# pc_rpi_healthypi_v3.net
KiCad netlist of a schematic drawn in EAGLE
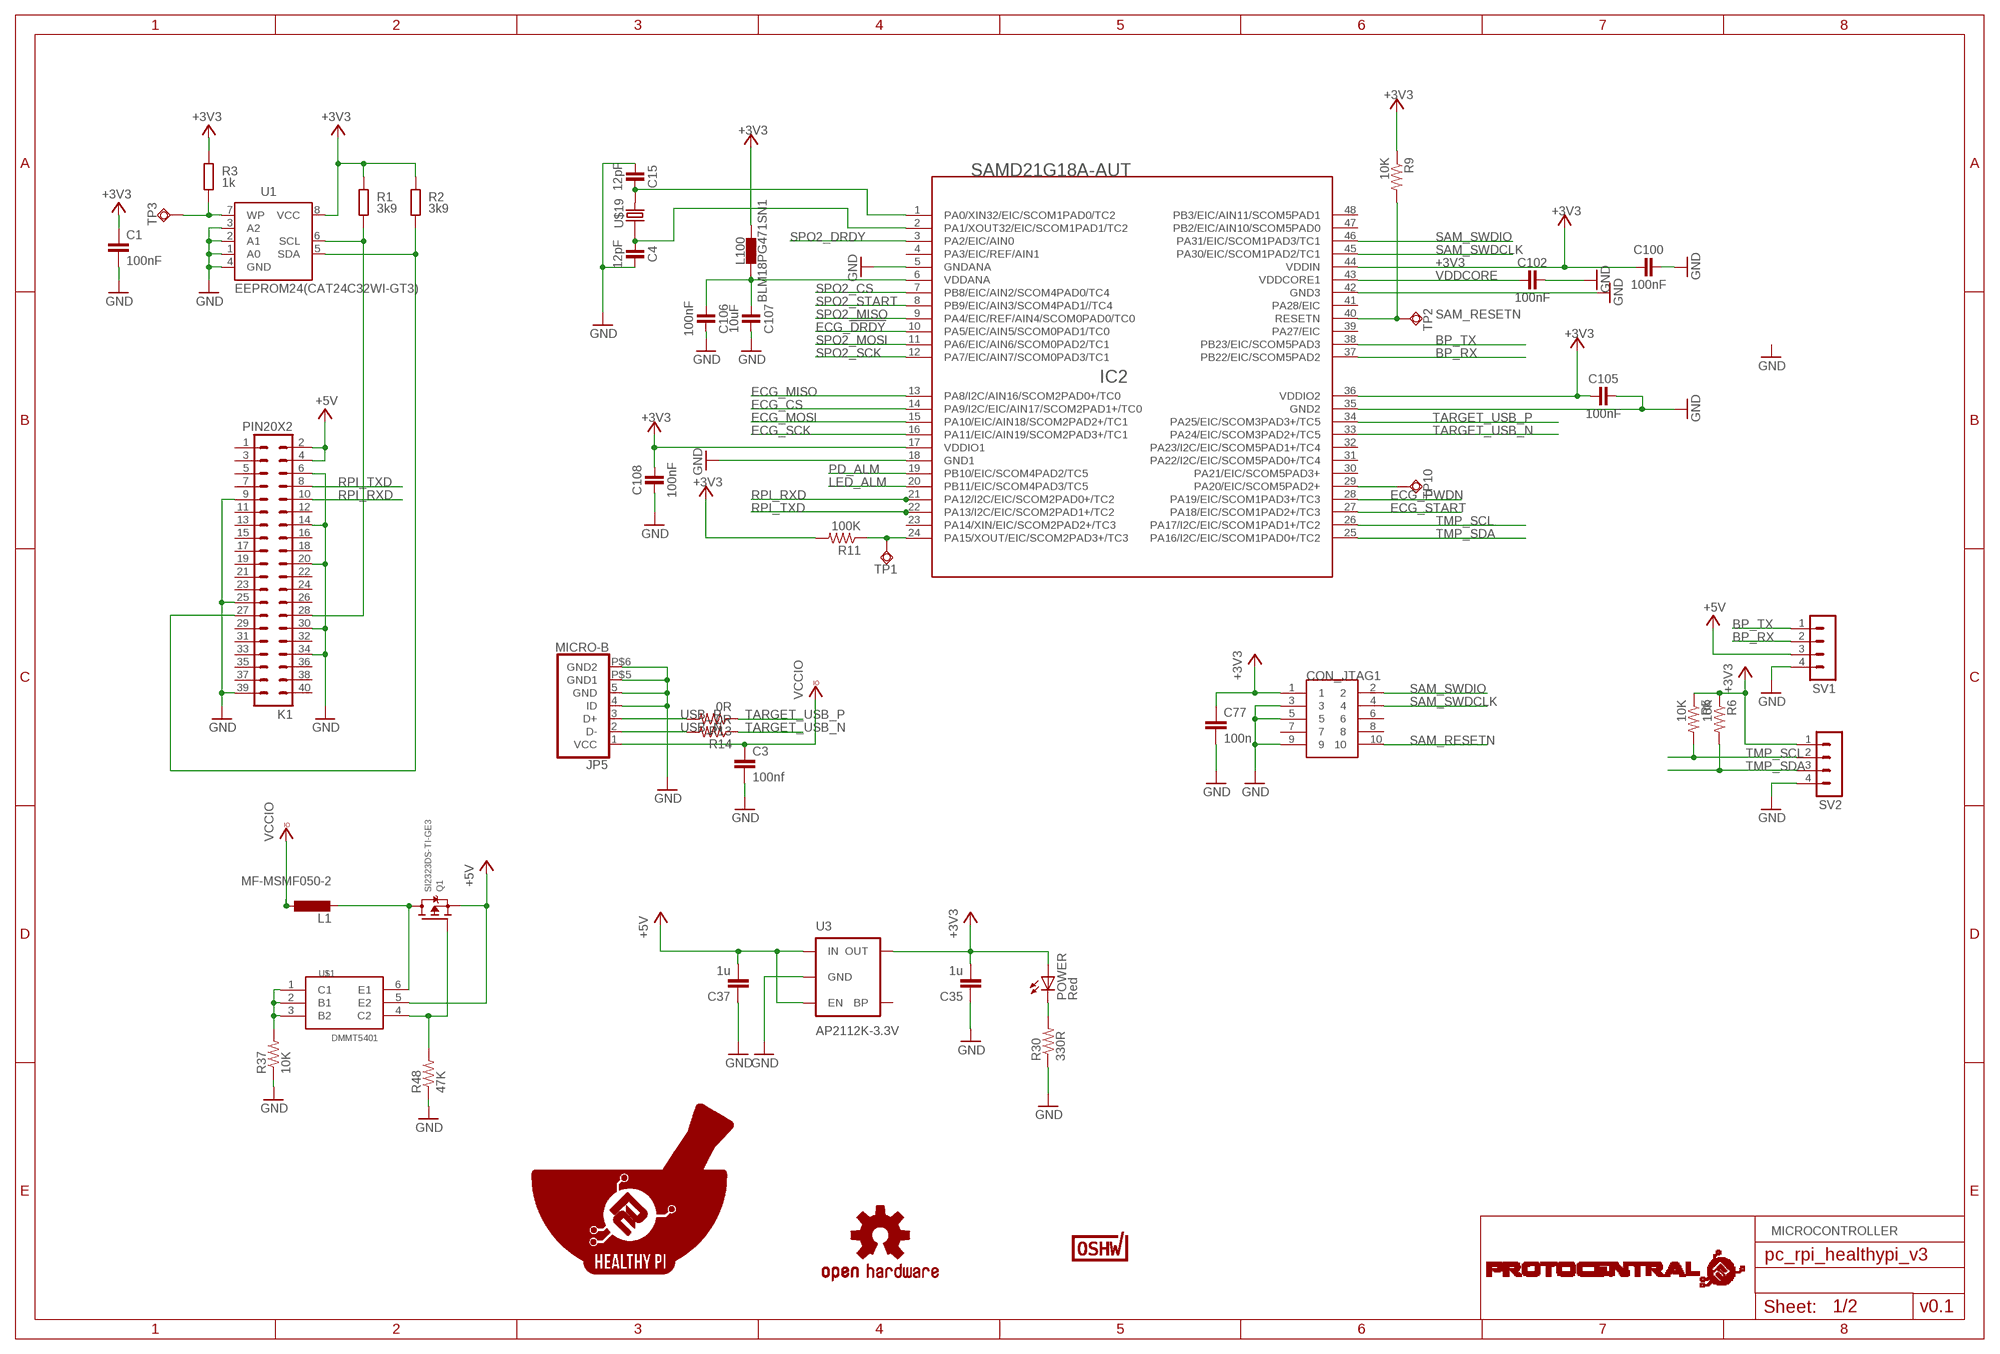
[diagram p0: schematic, sheet 1]
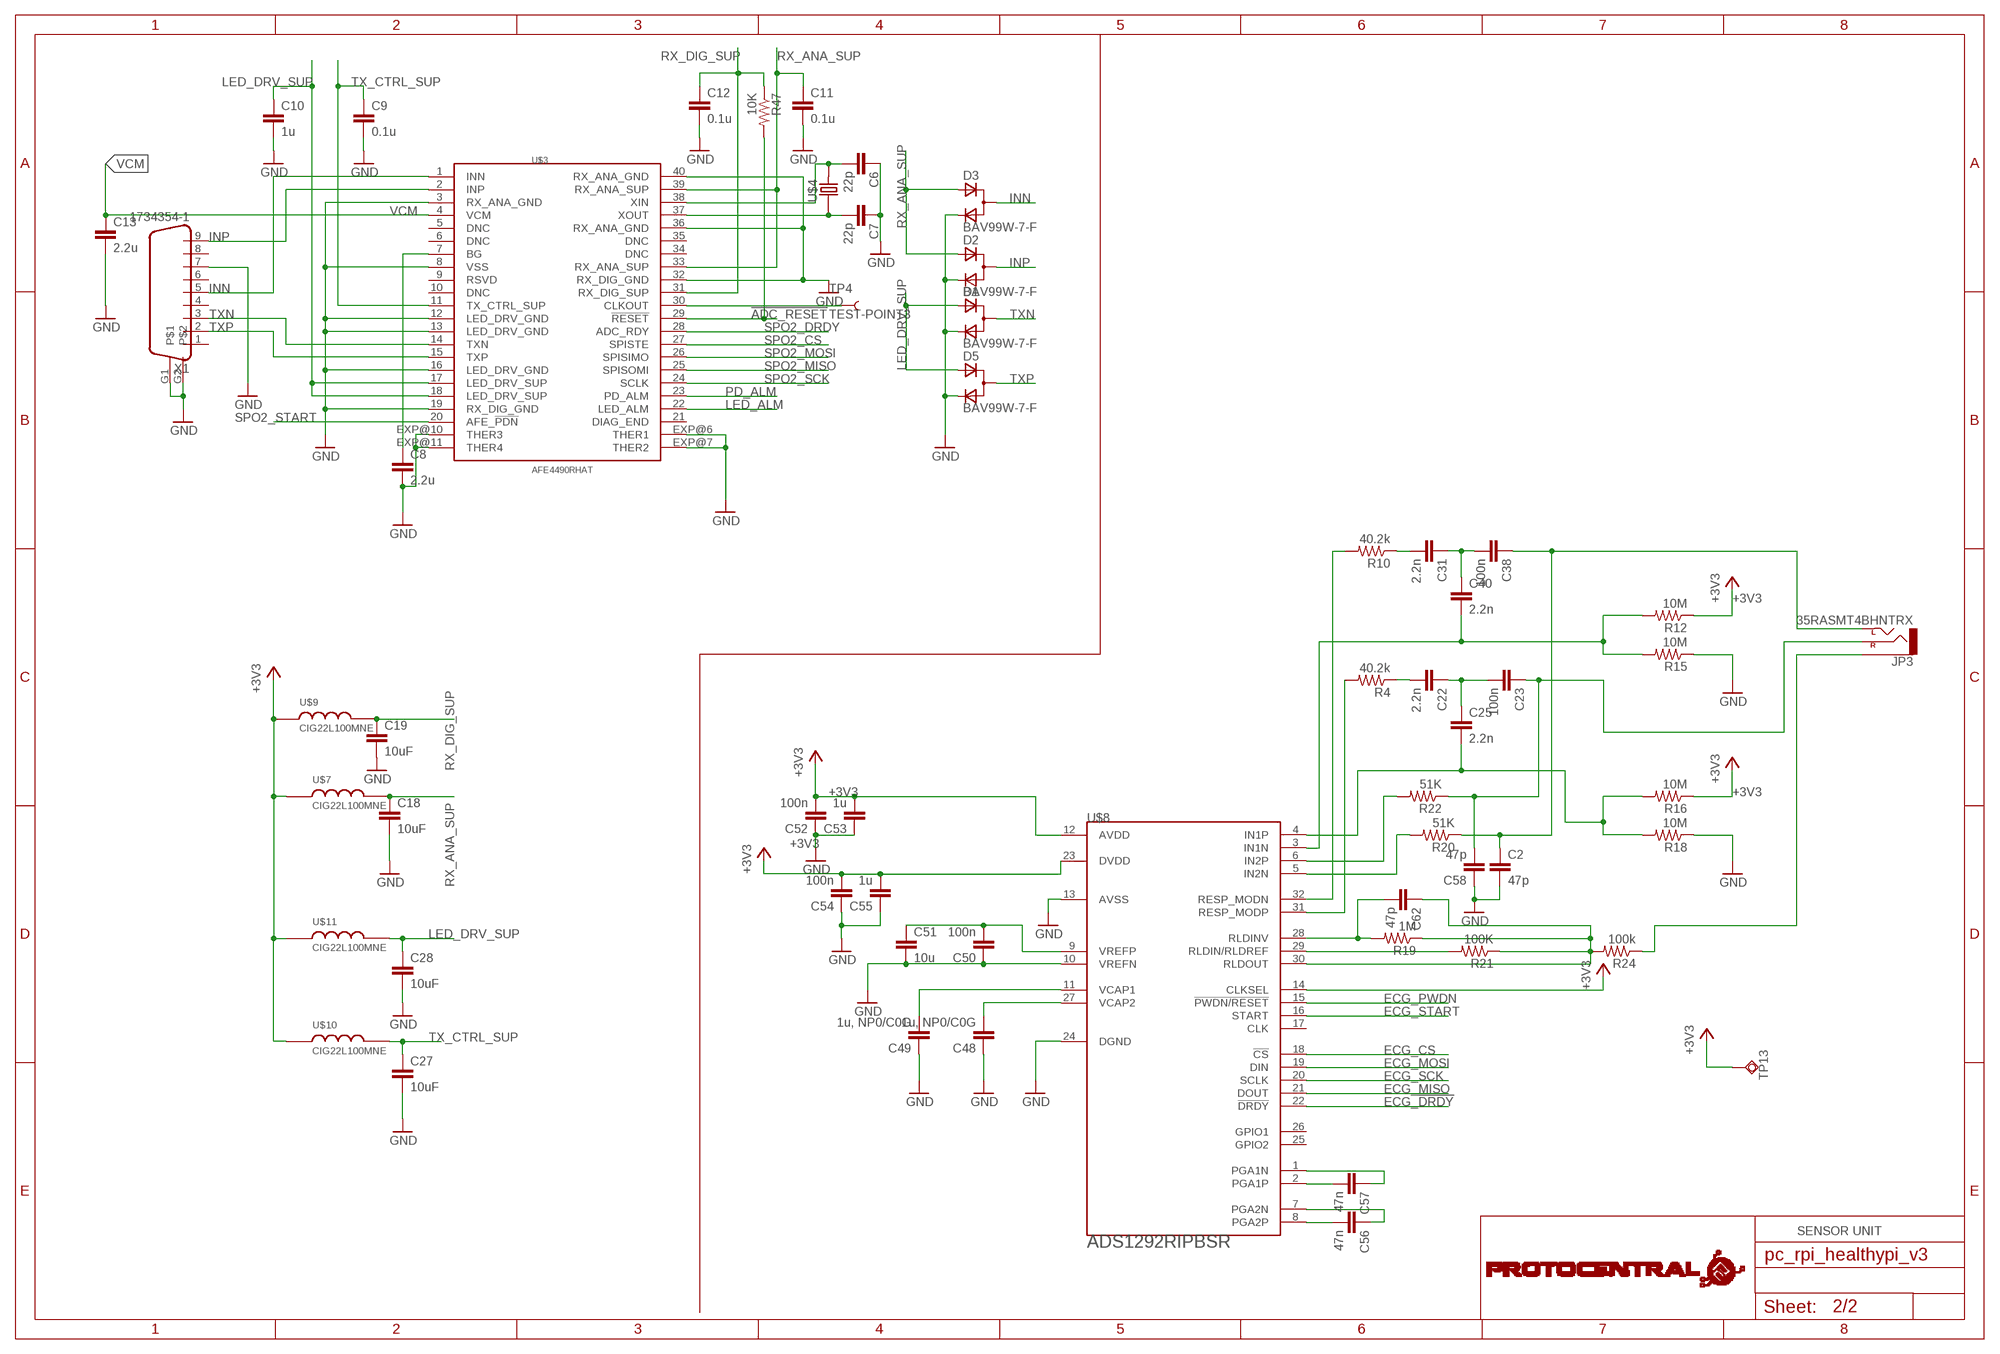
[diagram p1: schematic, sheet 2]

(export (version "E")
  (design (tool "Eeschema 10.0.6"))
  (components
    (comp (ref "C2")
      (value "47p")
      (footprint "eagle-import:C0402")
      (libsource (lib "eagle-import") (part "C-EUC0402"))
    )
    (comp (ref "C6")
      (value "22p")
      (footprint "eagle-import:C0402")
      (libsource (lib "eagle-import") (part "C-EUC0402"))
    )
    (comp (ref "C7")
      (value "22p")
      (footprint "eagle-import:C0402")
      (libsource (lib "eagle-import") (part "C-EUC0402"))
    )
    (comp (ref "C8")
      (value "2.2u")
      (footprint "eagle-import:C0402")
      (libsource (lib "eagle-import") (part "C-EUC0402"))
    )
    (comp (ref "C9")
      (value "0.1u")
      (footprint "eagle-import:C0402")
      (libsource (lib "eagle-import") (part "C-EUC0402"))
    )
    (comp (ref "C10")
      (value "1u")
      (footprint "eagle-import:C0805")
      (libsource (lib "eagle-import") (part "C-EUC0805"))
    )
    (comp (ref "C11")
      (value "0.1u")
      (footprint "eagle-import:C0402")
      (libsource (lib "eagle-import") (part "C-EUC0402"))
    )
    (comp (ref "C12")
      (value "0.1u")
      (footprint "eagle-import:C0402")
      (libsource (lib "eagle-import") (part "C-EUC0402"))
    )
    (comp (ref "C13")
      (value "2.2u")
      (footprint "eagle-import:C0402")
      (libsource (lib "eagle-import") (part "C-EUC0402"))
    )
    (comp (ref "C18")
      (value "10uF")
      (footprint "eagle-import:C0805")
      (libsource (lib "eagle-import") (part "C-EUC0805"))
    )
    (comp (ref "C19")
      (value "10uF")
      (footprint "eagle-import:C0805")
      (libsource (lib "eagle-import") (part "C-EUC0805"))
    )
    (comp (ref "C22")
      (value "2.2n")
      (footprint "eagle-import:C0402")
      (libsource (lib "eagle-import") (part "C-EUC0402"))
    )
    (comp (ref "C23")
      (value "100n")
      (footprint "eagle-import:C0402")
      (libsource (lib "eagle-import") (part "C-EUC0402"))
    )
    (comp (ref "C25")
      (value "2.2n")
      (footprint "eagle-import:C0402")
      (libsource (lib "eagle-import") (part "C-EUC0402"))
    )
    (comp (ref "C27")
      (value "10uF")
      (footprint "eagle-import:C0805")
      (libsource (lib "eagle-import") (part "C-EUC0805"))
    )
    (comp (ref "C28")
      (value "10uF")
      (footprint "eagle-import:C0805")
      (libsource (lib "eagle-import") (part "C-EUC0805"))
    )
    (comp (ref "C31")
      (value "2.2n")
      (footprint "eagle-import:C0402")
      (libsource (lib "eagle-import") (part "C-EUC0402"))
    )
    (comp (ref "C38")
      (value "100n")
      (footprint "eagle-import:C0402")
      (libsource (lib "eagle-import") (part "C-EUC0402"))
    )
    (comp (ref "C40")
      (value "2.2n")
      (footprint "eagle-import:C0402")
      (libsource (lib "eagle-import") (part "C-EUC0402"))
    )
    (comp (ref "C48")
      (value "1u, NP0/C0G")
      (footprint "eagle-import:C0402")
      (libsource (lib "eagle-import") (part "C-EUC0402"))
    )
    (comp (ref "C49")
      (value "1u, NP0/C0G")
      (footprint "eagle-import:C0402")
      (libsource (lib "eagle-import") (part "C-EUC0402"))
    )
    (comp (ref "C50")
      (value "100n")
      (footprint "eagle-import:C0402")
      (libsource (lib "eagle-import") (part "C-EUC0402"))
    )
    (comp (ref "C51")
      (value "10u")
      (footprint "eagle-import:C0603")
      (libsource (lib "eagle-import") (part "resistor_C-EUC0603"))
    )
    (comp (ref "C52")
      (value "100n")
      (footprint "eagle-import:C0402")
      (libsource (lib "eagle-import") (part "C-EUC0402"))
    )
    (comp (ref "C53")
      (value "1u")
      (footprint "eagle-import:C0402")
      (libsource (lib "eagle-import") (part "C-EUC0402"))
    )
    (comp (ref "C54")
      (value "100n")
      (footprint "eagle-import:C0402")
      (libsource (lib "eagle-import") (part "C-EUC0402"))
    )
    (comp (ref "C55")
      (value "1u")
      (footprint "eagle-import:C0402")
      (libsource (lib "eagle-import") (part "C-EUC0402"))
    )
    (comp (ref "C56")
      (value "47n")
      (footprint "eagle-import:C0402")
      (libsource (lib "eagle-import") (part "C-EUC0402"))
    )
    (comp (ref "C57")
      (value "47n")
      (footprint "eagle-import:C0402")
      (libsource (lib "eagle-import") (part "C-EUC0402"))
    )
    (comp (ref "C58")
      (value "47p")
      (footprint "eagle-import:C0402")
      (libsource (lib "eagle-import") (part "C-EUC0402"))
    )
    (comp (ref "C62")
      (value "47p")
      (footprint "eagle-import:C0402")
      (libsource (lib "eagle-import") (part "C-EUC0402"))
    )
    (comp (ref "D1")
      (value "BAV99W-7-F")
      (footprint "eagle-import:SOT323")
      (libsource (lib "eagle-import") (part "D_ACACSOT323"))
    )
    (comp (ref "D2")
      (value "BAV99W-7-F")
      (footprint "eagle-import:SOT323")
      (libsource (lib "eagle-import") (part "D_ACACSOT323"))
    )
    (comp (ref "D3")
      (value "BAV99W-7-F")
      (footprint "eagle-import:SOT323")
      (libsource (lib "eagle-import") (part "D_ACACSOT323"))
    )
    (comp (ref "D5")
      (value "BAV99W-7-F")
      (footprint "eagle-import:SOT323")
      (libsource (lib "eagle-import") (part "D_ACACSOT323"))
    )
    (comp (ref "JP3")
      (value "35RASMT4BHNTRX")
      (footprint "eagle-import:AUDIO-JACK-3.5MM-SMD")
      (libsource (lib "eagle-import") (part "AUDIO-JACKSMD2"))
    )
    (comp (ref "R4")
      (value "40.2k")
      (footprint "eagle-import:R0402")
      (libsource (lib "eagle-import") (part "R-US_R0402"))
    )
    (comp (ref "R10")
      (value "40.2k")
      (footprint "eagle-import:R0402")
      (libsource (lib "eagle-import") (part "R-US_R0402"))
    )
    (comp (ref "R12")
      (value "10M")
      (footprint "eagle-import:R0402")
      (libsource (lib "eagle-import") (part "R-US_R0402"))
    )
    (comp (ref "R15")
      (value "10M")
      (footprint "eagle-import:R0402")
      (libsource (lib "eagle-import") (part "R-US_R0402"))
    )
    (comp (ref "R16")
      (value "10M")
      (footprint "eagle-import:R0402")
      (libsource (lib "eagle-import") (part "R-US_R0402"))
    )
    (comp (ref "R18")
      (value "10M")
      (footprint "eagle-import:R0402")
      (libsource (lib "eagle-import") (part "R-US_R0402"))
    )
    (comp (ref "R19")
      (value "1M")
      (footprint "eagle-import:R0402")
      (libsource (lib "eagle-import") (part "R-US_R0402"))
    )
    (comp (ref "R20")
      (value "51K")
      (footprint "eagle-import:R0402")
      (libsource (lib "eagle-import") (part "R-US_R0402"))
    )
    (comp (ref "R21")
      (value "100K")
      (footprint "eagle-import:R0402")
      (libsource (lib "eagle-import") (part "R-US_R0402"))
    )
    (comp (ref "R22")
      (value "51K")
      (footprint "eagle-import:R0402")
      (libsource (lib "eagle-import") (part "R-US_R0402"))
    )
    (comp (ref "R24")
      (value "100k")
      (footprint "eagle-import:R0402")
      (libsource (lib "eagle-import") (part "R-US_R0402"))
    )
    (comp (ref "R47")
      (value "10K")
      (footprint "eagle-import:R0402")
      (libsource (lib "eagle-import") (part "R-US_R0402"))
    )
    (comp (ref "TP4")
      (value "TEST-POINT3")
      (footprint "eagle-import:PAD.03X.03")
      (libsource (lib "eagle-import") (part "TEST-POINT3"))
    )
    (comp (ref "TP13")
      (value "TPSQB1,27")
      (footprint "eagle-import:B1,27")
      (libsource (lib "eagle-import") (part "TPSQB1,27"))
    )
    (comp (ref "U$2")
      (value "PROTY_LOGO_WITH_TEXT")
      (footprint "eagle-import:PROTY_WITH_TEXT")
      (libsource (lib "eagle-import") (part "PROTY_LOGO_WITH_TEXT"))
    )
    (comp (ref "U$3")
      (value "AFE4490RHAT")
      (footprint "eagle-import:QFN-40")
      (libsource (lib "eagle-import") (part "AFE4400"))
    )
    (comp (ref "U$4")
      (value "ABM3")
      (footprint "eagle-import:ABM3")
      (libsource (lib "eagle-import") (part "ABM3"))
    )
    (comp (ref "U$7")
      (value "CIG22L100MNE")
      (footprint "eagle-import:LPS")
      (libsource (lib "eagle-import") (part "LPS"))
    )
    (comp (ref "U$8")
      (value "ADS1292RIPBSR")
      (footprint "eagle-import:SQFP-S-5X5-32")
      (libsource (lib "eagle-import") (part "ADS1292R-TQFP"))
    )
    (comp (ref "U$9")
      (value "CIG22L100MNE")
      (footprint "eagle-import:LPS")
      (libsource (lib "eagle-import") (part "LPS"))
    )
    (comp (ref "U$10")
      (value "CIG22L100MNE")
      (footprint "eagle-import:LPS")
      (libsource (lib "eagle-import") (part "LPS"))
    )
    (comp (ref "U$11")
      (value "CIG22L100MNE")
      (footprint "eagle-import:LPS")
      (libsource (lib "eagle-import") (part "LPS"))
    )
    (comp (ref "X1")
      (value "1734354-1")
      (footprint "eagle-import:DB9-STRIGHT")
      (libsource (lib "eagle-import") (part "DB9_STRIGHT"))
    )
    (comp (ref "C1")
      (value "100nF")
      (footprint "eagle-import:C0805K")
      (libsource (lib "eagle-import") (part "resistor_C-EUC0805K"))
    )
    (comp (ref "C3")
      (value "100nf")
      (footprint "eagle-import:C0402")
      (libsource (lib "eagle-import") (part "C-EUC0402"))
    )
    (comp (ref "C4")
      (value "12pF")
      (footprint "eagle-import:C0402")
      (libsource (lib "eagle-import") (part "CAPACITORS-0402"))
    )
    (comp (ref "C15")
      (value "12pF")
      (footprint "eagle-import:C0402")
      (libsource (lib "eagle-import") (part "CAPACITORS-0402"))
    )
    (comp (ref "C35")
      (value "1u")
      (footprint "eagle-import:C0402")
      (libsource (lib "eagle-import") (part "C-EUC0402"))
    )
    (comp (ref "C37")
      (value "1u")
      (footprint "eagle-import:C0402")
      (libsource (lib "eagle-import") (part "C-EUC0402"))
    )
    (comp (ref "C77")
      (value "100n")
      (footprint "eagle-import:C0805")
      (libsource (lib "eagle-import") (part "C-EUC0805"))
    )
    (comp (ref "C100")
      (value "100nF")
      (footprint "eagle-import:C0805")
      (libsource (lib "eagle-import") (part "CAPACITORS-0805"))
    )
    (comp (ref "C102")
      (value "100nF")
      (footprint "eagle-import:C0805")
      (libsource (lib "eagle-import") (part "CAPACITORS-0805"))
    )
    (comp (ref "C105")
      (value "100nF")
      (footprint "eagle-import:C0805")
      (libsource (lib "eagle-import") (part "CAPACITORS-0805"))
    )
    (comp (ref "C106")
      (value "100nF")
      (footprint "eagle-import:C0805")
      (libsource (lib "eagle-import") (part "CAPACITORS-0805"))
    )
    (comp (ref "C107")
      (value "10uF")
      (footprint "eagle-import:C0805")
      (libsource (lib "eagle-import") (part "CAPACITORS-0805"))
    )
    (comp (ref "C108")
      (value "100nF")
      (footprint "eagle-import:C0805")
      (libsource (lib "eagle-import") (part "CAPACITORS-0805"))
    )
    (comp (ref "CON_JTAG1")
      (value "HDR-SMT-50MIL/5X2(20021121-00010C4LF)")
      (footprint "eagle-import:HDR-SMT-50MIL_5X2")
      (libsource (lib "eagle-import") (part "HDR-SMT-50MIL/5X2"))
    )
    (comp (ref "IC2")
      (value "SAMD21G18A-AUT")
      (footprint "eagle-import:TQFP48")
      (libsource (lib "eagle-import") (part "SAMD21G18A"))
    )
    (comp (ref "JP5")
      (value "MICRO-B")
      (footprint "eagle-import:MICRO-B")
      (libsource (lib "eagle-import") (part "MICRO-B"))
    )
    (comp (ref "K1")
      (value "PIN20X2")
      (footprint "eagle-import:PIN_20X2")
      (libsource (lib "eagle-import") (part "PIN20X2"))
    )
    (comp (ref "L1")
      (value "MF-MSMF050-2")
      (footprint "eagle-import:L1812")
      (libsource (lib "eagle-import") (part "L-EUL1812"))
    )
    (comp (ref "L100")
      (value "BLM18PG471SN1")
      (footprint "eagle-import:C0603")
      (libsource (lib "eagle-import") (part "INDUCTOR-0603"))
    )
    (comp (ref "POWER")
      (value "Red")
      (footprint "eagle-import:CHIPLED_0603")
      (libsource (lib "eagle-import") (part "LEDCHIPLED_0603"))
    )
    (comp (ref "Q1")
      (value "SI2323DS-TI-GE3")
      (footprint "eagle-import:SOT23-R")
      (libsource (lib "eagle-import") (part "MOSFET-P"))
    )
    (comp (ref "R1")
      (value "3k9")
      (footprint "eagle-import:M0805")
      (fields (field (name "TOLERANCE") "5%"))
      (libsource (lib "eagle-import") (part "R-EU_M0805"))
    )
    (comp (ref "R2")
      (value "3k9")
      (footprint "eagle-import:M0805")
      (fields (field (name "TOLERANCE") "5%"))
      (libsource (lib "eagle-import") (part "R-EU_M0805"))
    )
    (comp (ref "R3")
      (value "1k")
      (footprint "eagle-import:M0805")
      (fields (field (name "TOLERANCE") "5%"))
      (libsource (lib "eagle-import") (part "R-EU_M0805"))
    )
    (comp (ref "R5")
      (value "10K")
      (footprint "eagle-import:R0402")
      (libsource (lib "eagle-import") (part "R-US_R0402"))
    )
    (comp (ref "R6")
      (value "10K")
      (footprint "eagle-import:R0402")
      (libsource (lib "eagle-import") (part "R-US_R0402"))
    )
    (comp (ref "R9")
      (value "10K")
      (footprint "eagle-import:R0805")
      (libsource (lib "eagle-import") (part "R-US_R0805"))
    )
    (comp (ref "R11")
      (value "100K")
      (footprint "eagle-import:R0805")
      (libsource (lib "eagle-import") (part "R-US_R0805"))
    )
    (comp (ref "R13")
      (value "0R")
      (footprint "eagle-import:R0402")
      (libsource (lib "eagle-import") (part "R-US_R0402"))
    )
    (comp (ref "R14")
      (value "0R")
      (footprint "eagle-import:R0402")
      (libsource (lib "eagle-import") (part "R-US_R0402"))
    )
    (comp (ref "R30")
      (value "330R")
      (footprint "eagle-import:R0402")
      (libsource (lib "eagle-import") (part "R-US_R0402"))
    )
    (comp (ref "R37")
      (value "10K")
      (footprint "eagle-import:R0805")
      (libsource (lib "eagle-import") (part "R-US_R0805"))
    )
    (comp (ref "R48")
      (value "47K")
      (footprint "eagle-import:R0805")
      (libsource (lib "eagle-import") (part "R-US_R0805"))
    )
    (comp (ref "SV1")
      (value "MA04-1")
      (footprint "eagle-import:MA04-1")
      (libsource (lib "eagle-import") (part "MA04-1"))
    )
    (comp (ref "SV2")
      (value "MA04-1")
      (footprint "eagle-import:MA04-1")
      (libsource (lib "eagle-import") (part "MA04-1"))
    )
    (comp (ref "TP1")
      (value "TPSQB1,27")
      (footprint "eagle-import:B1,27")
      (libsource (lib "eagle-import") (part "TPSQB1,27"))
    )
    (comp (ref "TP2")
      (value "TPSQB1,27")
      (footprint "eagle-import:B1,27")
      (libsource (lib "eagle-import") (part "TPSQB1,27"))
    )
    (comp (ref "TP3")
      (value "TPSQB1,27")
      (footprint "eagle-import:B1,27")
      (libsource (lib "eagle-import") (part "TPSQB1,27"))
    )
    (comp (ref "TP10")
      (value "TPSQB1,27")
      (footprint "eagle-import:B1,27")
      (libsource (lib "eagle-import") (part "TPSQB1,27"))
    )
    (comp (ref "U$1")
      (value "DMMT5401")
      (footprint "eagle-import:SOT26")
      (libsource (lib "eagle-import") (part "DMMT5401"))
    )
    (comp (ref "U$5")
      (value "OSHW-LOGOM")
      (footprint "eagle-import:OSHW-LOGO-M")
      (libsource (lib "eagle-import") (part "OSHW-LOGOM"))
    )
    (comp (ref "U$6")
      (value "PROTY_LOGO_WITH_TEXT")
      (footprint "eagle-import:PROTY_WITH_TEXT")
      (libsource (lib "eagle-import") (part "PROTY_LOGO_WITH_TEXT"))
    )
    (comp (ref "U$13")
      (value "CERT-SMALL")
      (footprint "eagle-import:CERT-SMALL-SILK")
      (libsource (lib "eagle-import") (part "CERT-SMALL"))
    )
    (comp (ref "U$15")
      (value "HEALTHYPI")
      (footprint "eagle-import:HEALTHYPI")
      (libsource (lib "eagle-import") (part "HEALTHYPI"))
    )
    (comp (ref "U$19")
      (value "520-327-12.5-34B(32.768KHZ)")
      (footprint "eagle-import:ECX-31B")
      (libsource (lib "eagle-import") (part "ECS-X-34B"))
    )
    (comp (ref "U1")
      (value "EEPROM24(CAT24C32WI-GT3)")
      (footprint "eagle-import:SOIC8")
      (libsource (lib "eagle-import") (part "EEPROM24"))
    )
    (comp (ref "U3")
      (value "AP2112K-3.3V")
      (footprint "eagle-import:SOT23-5")
      (libsource (lib "eagle-import") (part "V_REG_LDOSMD"))
    )
  )
  (nets
    (net (code "1") (name "+3V3") (class "Default")
      (node (ref "C1") (pin "1") (pinfunction "1_1") (pintype "passive"))
      (node (ref "C100") (pin "1") (pinfunction "1_1") (pintype "passive"))
      (node (ref "C105") (pin "1") (pinfunction "1_1") (pintype "passive"))
      (node (ref "C108") (pin "2") (pinfunction "2_2") (pintype "passive"))
      (node (ref "C35") (pin "2") (pinfunction "2_2") (pintype "passive"))
      (node (ref "C52") (pin "2") (pinfunction "2_2") (pintype "passive"))
      (node (ref "C53") (pin "2") (pinfunction "2_2") (pintype "passive"))
      (node (ref "C54") (pin "2") (pinfunction "2_2") (pintype "passive"))
      (node (ref "C55") (pin "2") (pinfunction "2_2") (pintype "passive"))
      (node (ref "C77") (pin "1") (pinfunction "1_1") (pintype "passive"))
      (node (ref "CON_JTAG1") (pin "1") (pinfunction "1_1") (pintype "bidirectional"))
      (node (ref "IC2") (pin "17") (pinfunction "VDDIO1_17") (pintype "power_in"))
      (node (ref "IC2") (pin "36") (pinfunction "VDDIO2_36") (pintype "power_in"))
      (node (ref "IC2") (pin "44") (pinfunction "VDDIN_44") (pintype "power_in"))
      (node (ref "L100") (pin "2") (pinfunction "2_2") (pintype "passive"))
      (node (ref "POWER") (pin "A") (pinfunction "A_A") (pintype "passive"))
      (node (ref "R1") (pin "2") (pinfunction "2_2") (pintype "passive"))
      (node (ref "R11") (pin "2") (pinfunction "2_2") (pintype "passive"))
      (node (ref "R12") (pin "1") (pinfunction "1_1") (pintype "passive"))
      (node (ref "R16") (pin "1") (pinfunction "1_1") (pintype "passive"))
      (node (ref "R2") (pin "2") (pinfunction "2_2") (pintype "passive"))
      (node (ref "R3") (pin "2") (pinfunction "2_2") (pintype "passive"))
      (node (ref "R5") (pin "1") (pinfunction "1_1") (pintype "passive"))
      (node (ref "R6") (pin "1") (pinfunction "1_1") (pintype "passive"))
      (node (ref "R9") (pin "1") (pinfunction "1_1") (pintype "passive"))
      (node (ref "SV2") (pin "1") (pinfunction "1_1") (pintype "passive"))
      (node (ref "TP13") (pin "TP") (pinfunction "TP_TP") (pintype "input"))
      (node (ref "U$10") (pin "1") (pinfunction "P$1_1") (pintype "bidirectional"))
      (node (ref "U$11") (pin "1") (pinfunction "P$1_1") (pintype "bidirectional"))
      (node (ref "U$7") (pin "1") (pinfunction "P$1_1") (pintype "bidirectional"))
      (node (ref "U$8") (pin "12") (pinfunction "AVDD_12") (pintype "power_in"))
      (node (ref "U$8") (pin "14") (pinfunction "CLKSEL_14") (pintype "bidirectional"))
      (node (ref "U$8") (pin "23") (pinfunction "DVDD_23") (pintype "power_in"))
      (node (ref "U$9") (pin "1") (pinfunction "P$1_1") (pintype "bidirectional"))
      (node (ref "U1") (pin "8") (pinfunction "VCC_8") (pintype "power_in"))
      (node (ref "U3") (pin "5") (pinfunction "OUT_5") (pintype "passive"))
    )
    (net (code "2") (name "+5V") (class "Default")
      (node (ref "C37") (pin "2") (pinfunction "2_2") (pintype "passive"))
      (node (ref "K1") (pin "2") (pinfunction "2_2") (pintype "passive"))
      (node (ref "K1") (pin "4") (pinfunction "4_4") (pintype "passive"))
      (node (ref "Q1") (pin "2") (pinfunction "S_2") (pintype "passive"))
      (node (ref "SV1") (pin "3") (pinfunction "3_3") (pintype "passive"))
      (node (ref "U$1") (pin "5") (pinfunction "E2_5") (pintype "bidirectional"))
      (node (ref "U3") (pin "1") (pinfunction "IN_1") (pintype "input"))
      (node (ref "U3") (pin "3") (pinfunction "EN_3") (pintype "input"))
    )
    (net (code "3") (name "BP_RX") (class "Default")
      (node (ref "IC2") (pin "37") (pinfunction "PB22/EIC/SCOM5PAD2_37") (pintype "bidirectional"))
      (node (ref "SV1") (pin "2") (pinfunction "2_2") (pintype "passive"))
    )
    (net (code "4") (name "BP_TX") (class "Default")
      (node (ref "IC2") (pin "38") (pinfunction "PB23/EIC/SCOM5PAD3_38") (pintype "bidirectional"))
      (node (ref "SV1") (pin "1") (pinfunction "1_1") (pintype "passive"))
    )
    (net (code "5") (name "ECG_CS") (class "Default")
      (node (ref "IC2") (pin "14") (pinfunction "PA9/I2C/EIC/AIN17/SCOM2PAD1+/TC0_14") (pintype "bidirectional"))
      (node (ref "U$8") (pin "18") (pinfunction "~{CS}_18") (pintype "bidirectional"))
    )
    (net (code "6") (name "ECG_MISO") (class "Default")
      (node (ref "IC2") (pin "13") (pinfunction "PA8/I2C/AIN16/SCOM2PAD0+/TC0_13") (pintype "bidirectional"))
      (node (ref "U$8") (pin "21") (pinfunction "DOUT_21") (pintype "bidirectional"))
    )
    (net (code "7") (name "ECG_MOSI") (class "Default")
      (node (ref "IC2") (pin "15") (pinfunction "PA10/EIC/AIN18/SCOM2PAD2+/TC1_15") (pintype "bidirectional"))
      (node (ref "U$8") (pin "19") (pinfunction "DIN_19") (pintype "bidirectional"))
    )
    (net (code "8") (name "ECG_PWDN") (class "Default")
      (node (ref "IC2") (pin "28") (pinfunction "PA19/EIC/SCOM1PAD3+/TC3_28") (pintype "bidirectional"))
      (node (ref "U$8") (pin "15") (pinfunction "~{PWDN/RESET}_15") (pintype "bidirectional"))
    )
    (net (code "9") (name "ECG_SCK") (class "Default")
      (node (ref "IC2") (pin "16") (pinfunction "PA11/EIC/AIN19/SCOM2PAD3+/TC1_16") (pintype "bidirectional"))
      (node (ref "U$8") (pin "20") (pinfunction "SCLK_20") (pintype "bidirectional"))
    )
    (net (code "10") (name "ECG_START") (class "Default")
      (node (ref "IC2") (pin "27") (pinfunction "PA18/EIC/SCOM1PAD2+/TC3_27") (pintype "bidirectional"))
      (node (ref "U$8") (pin "16") (pinfunction "START_16") (pintype "bidirectional"))
    )
    (net (code "11") (name "ECG_~{DRDY}") (class "Default")
      (node (ref "IC2") (pin "10") (pinfunction "PA5/EIC/AIN5/SCOM0PAD1/TC0_10") (pintype "bidirectional"))
      (node (ref "U$8") (pin "22") (pinfunction "~{DRDY}_22") (pintype "bidirectional"))
    )
    (net (code "12") (name "GND") (class "Default")
      (node (ref "C1") (pin "2") (pinfunction "2_2") (pintype "passive"))
      (node (ref "C10") (pin "2") (pinfunction "2_2") (pintype "passive"))
      (node (ref "C100") (pin "2") (pinfunction "2_2") (pintype "passive"))
      (node (ref "C102") (pin "2") (pinfunction "2_2") (pintype "passive"))
      (node (ref "C105") (pin "2") (pinfunction "2_2") (pintype "passive"))
      (node (ref "C106") (pin "2") (pinfunction "2_2") (pintype "passive"))
      (node (ref "C107") (pin "2") (pinfunction "2_2") (pintype "passive"))
      (node (ref "C108") (pin "1") (pinfunction "1_1") (pintype "passive"))
      (node (ref "C11") (pin "2") (pinfunction "2_2") (pintype "passive"))
      (node (ref "C12") (pin "2") (pinfunction "2_2") (pintype "passive"))
      (node (ref "C13") (pin "2") (pinfunction "2_2") (pintype "passive"))
      (node (ref "C15") (pin "1") (pinfunction "1_1") (pintype "passive"))
      (node (ref "C18") (pin "2") (pinfunction "2_2") (pintype "passive"))
      (node (ref "C19") (pin "2") (pinfunction "2_2") (pintype "passive"))
      (node (ref "C2") (pin "2") (pinfunction "2_2") (pintype "passive"))
      (node (ref "C27") (pin "2") (pinfunction "2_2") (pintype "passive"))
      (node (ref "C28") (pin "2") (pinfunction "2_2") (pintype "passive"))
      (node (ref "C3") (pin "2") (pinfunction "2_2") (pintype "passive"))
      (node (ref "C35") (pin "1") (pinfunction "1_1") (pintype "passive"))
      (node (ref "C37") (pin "1") (pinfunction "1_1") (pintype "passive"))
      (node (ref "C4") (pin "2") (pinfunction "2_2") (pintype "passive"))
      (node (ref "C48") (pin "1") (pinfunction "1_1") (pintype "passive"))
      (node (ref "C49") (pin "1") (pinfunction "1_1") (pintype "passive"))
      (node (ref "C50") (pin "1") (pinfunction "1_1") (pintype "passive"))
      (node (ref "C51") (pin "2") (pinfunction "2_2") (pintype "passive"))
      (node (ref "C52") (pin "1") (pinfunction "1_1") (pintype "passive"))
      (node (ref "C53") (pin "1") (pinfunction "1_1") (pintype "passive"))
      (node (ref "C54") (pin "1") (pinfunction "1_1") (pintype "passive"))
      (node (ref "C55") (pin "1") (pinfunction "1_1") (pintype "passive"))
      (node (ref "C58") (pin "1") (pinfunction "1_1") (pintype "passive"))
      (node (ref "C6") (pin "1") (pinfunction "1_1") (pintype "passive"))
      (node (ref "C7") (pin "1") (pinfunction "1_1") (pintype "passive"))
      (node (ref "C77") (pin "2") (pinfunction "2_2") (pintype "passive"))
      (node (ref "C8") (pin "2") (pinfunction "2_2") (pintype "passive"))
      (node (ref "C9") (pin "2") (pinfunction "2_2") (pintype "passive"))
      (node (ref "CON_JTAG1") (pin "3") (pinfunction "3_3") (pintype "bidirectional"))
      (node (ref "CON_JTAG1") (pin "5") (pinfunction "5_5") (pintype "bidirectional"))
      (node (ref "CON_JTAG1") (pin "9") (pinfunction "9_9") (pintype "bidirectional"))
      (node (ref "D1") (pin "2") (pinfunction "C_2") (pintype "passive"))
      (node (ref "D2") (pin "2") (pinfunction "C_2") (pintype "passive"))
      (node (ref "D3") (pin "2") (pinfunction "C_2") (pintype "passive"))
      (node (ref "D5") (pin "2") (pinfunction "C_2") (pintype "passive"))
      (node (ref "IC2") (pin "18") (pinfunction "GND1_18") (pintype "power_in"))
      (node (ref "IC2") (pin "35") (pinfunction "GND2_35") (pintype "power_in"))
      (node (ref "IC2") (pin "42") (pinfunction "GND3_42") (pintype "power_in"))
      (node (ref "IC2") (pin "5") (pinfunction "GNDANA_5") (pintype "power_in"))
      (node (ref "JP5") (pin "4") (pinfunction "ID_4") (pintype "bidirectional"))
      (node (ref "JP5") (pin "5") (pinfunction "GND_5") (pintype "bidirectional"))
      (node (ref "JP5") (pin "P$5") (pinfunction "GND1_P$5") (pintype "bidirectional"))
      (node (ref "JP5") (pin "P$6") (pinfunction "GND2_P$6") (pintype "bidirectional"))
      (node (ref "K1") (pin "14") (pinfunction "14_14") (pintype "passive"))
      (node (ref "K1") (pin "20") (pinfunction "20_20") (pintype "passive"))
      (node (ref "K1") (pin "25") (pinfunction "25_25") (pintype "passive"))
      (node (ref "K1") (pin "30") (pinfunction "30_30") (pintype "passive"))
      (node (ref "K1") (pin "34") (pinfunction "34_34") (pintype "passive"))
      (node (ref "K1") (pin "39") (pinfunction "39_39") (pintype "passive"))
      (node (ref "K1") (pin "6") (pinfunction "6_6") (pintype "passive"))
      (node (ref "K1") (pin "9") (pinfunction "9_9") (pintype "passive"))
      (node (ref "R15") (pin "1") (pinfunction "1_1") (pintype "passive"))
      (node (ref "R18") (pin "1") (pinfunction "1_1") (pintype "passive"))
      (node (ref "R30") (pin "1") (pinfunction "1_1") (pintype "passive"))
      (node (ref "R37") (pin "1") (pinfunction "1_1") (pintype "passive"))
      (node (ref "R48") (pin "1") (pinfunction "1_1") (pintype "passive"))
      (node (ref "SV1") (pin "4") (pinfunction "4_4") (pintype "passive"))
      (node (ref "SV2") (pin "4") (pinfunction "4_4") (pintype "passive"))
      (node (ref "U$3") (pin "12") (pinfunction "LED_DRV_GND_12") (pintype "bidirectional"))
      (node (ref "U$3") (pin "13") (pinfunction "LED_DRV_GND_13") (pintype "bidirectional"))
      (node (ref "U$3") (pin "16") (pinfunction "LED_DRV_GND_16") (pintype "bidirectional"))
      (node (ref "U$3") (pin "19") (pinfunction "RX_DIG_GND_19") (pintype "bidirectional"))
      (node (ref "U$3") (pin "3") (pinfunction "RX_ANA_GND_3") (pintype "bidirectional"))
      (node (ref "U$3") (pin "32") (pinfunction "RX_DIG_GND_32") (pintype "bidirectional"))
      (node (ref "U$3") (pin "36") (pinfunction "RX_ANA_GND_36") (pintype "bidirectional"))
      (node (ref "U$3") (pin "40") (pinfunction "RX_ANA_GND_40") (pintype "bidirectional"))
      (node (ref "U$3") (pin "8") (pinfunction "VSS_8") (pintype "bidirectional"))
      (node (ref "U$3") (pin "EXP@10") (pinfunction "THER3_EXP@10") (pintype "bidirectional"))
      (node (ref "U$3") (pin "EXP@11") (pinfunction "THER4_EXP@11") (pintype "bidirectional"))
      (node (ref "U$3") (pin "EXP@6") (pinfunction "THER1_EXP@6") (pintype "bidirectional"))
      (node (ref "U$3") (pin "EXP@7") (pinfunction "THER2_EXP@7") (pintype "bidirectional"))
      (node (ref "U$8") (pin "10") (pinfunction "VREFN_10") (pintype "bidirectional"))
      (node (ref "U$8") (pin "13") (pinfunction "AVSS_13") (pintype "bidirectional"))
      (node (ref "U$8") (pin "24") (pinfunction "DGND_24") (pintype "bidirectional"))
      (node (ref "U1") (pin "1") (pinfunction "A0_1") (pintype "input"))
      (node (ref "U1") (pin "2") (pinfunction "A1_2") (pintype "input"))
      (node (ref "U1") (pin "3") (pinfunction "A2_3") (pintype "input"))
      (node (ref "U1") (pin "4") (pinfunction "GND_4") (pintype "power_in"))
      (node (ref "U3") (pin "2") (pinfunction "GND_2") (pintype "input"))
      (node (ref "X1") (pin "7") (pinfunction "7_7") (pintype "passive"))
      (node (ref "X1") (pin "G1") (pinfunction "P$1_G1") (pintype "bidirectional"))
      (node (ref "X1") (pin "G2") (pinfunction "P$2_G2") (pintype "bidirectional"))
    )
    (net (code "13") (name "INN") (class "Default")
      (node (ref "D3") (pin "1") (pinfunction "CA_1") (pintype "passive"))
      (node (ref "U$3") (pin "1") (pinfunction "INN_1") (pintype "bidirectional"))
      (node (ref "X1") (pin "5") (pinfunction "5_5") (pintype "passive"))
    )
    (net (code "14") (name "INP") (class "Default")
      (node (ref "D2") (pin "1") (pinfunction "CA_1") (pintype "passive"))
      (node (ref "U$3") (pin "2") (pinfunction "INP_2") (pintype "bidirectional"))
      (node (ref "X1") (pin "9") (pinfunction "9_9") (pintype "passive"))
    )
    (net (code "15") (name "LED_ALM") (class "Default")
      (node (ref "IC2") (pin "20") (pinfunction "PB11/EIC/SCOM4PAD3/TC5_20") (pintype "bidirectional"))
      (node (ref "U$3") (pin "22") (pinfunction "LED_ALM_22") (pintype "bidirectional"))
    )
    (net (code "16") (name "LED_DRV_SUP") (class "Default")
      (node (ref "C10") (pin "1") (pinfunction "1_1") (pintype "passive"))
      (node (ref "C28") (pin "1") (pinfunction "1_1") (pintype "passive"))
      (node (ref "D1") (pin "3") (pinfunction "A_3") (pintype "passive"))
      (node (ref "D5") (pin "3") (pinfunction "A_3") (pintype "passive"))
      (node (ref "U$11") (pin "2") (pinfunction "P$2_2") (pintype "bidirectional"))
      (node (ref "U$3") (pin "17") (pinfunction "LED_DRV_SUP_17") (pintype "bidirectional"))
      (node (ref "U$3") (pin "18") (pinfunction "LED_DRV_SUP_18") (pintype "bidirectional"))
    )
    (net (code "17") (name "Net-(C22-Pad1)") (class "Default")
      (node (ref "C22") (pin "1") (pinfunction "1_1") (pintype "passive"))
      (node (ref "C23") (pin "2") (pinfunction "2_2") (pintype "passive"))
      (node (ref "C25") (pin "1") (pinfunction "1_1") (pintype "passive"))
    )
    (net (code "18") (name "Net-(C22-Pad2)") (class "Default")
      (node (ref "C22") (pin "2") (pinfunction "2_2") (pintype "passive"))
      (node (ref "R4") (pin "1") (pinfunction "1_1") (pintype "passive"))
    )
    (net (code "19") (name "Net-(C31-Pad1)") (class "Default")
      (node (ref "C31") (pin "1") (pinfunction "1_1") (pintype "passive"))
      (node (ref "C38") (pin "2") (pinfunction "2_2") (pintype "passive"))
      (node (ref "C40") (pin "1") (pinfunction "1_1") (pintype "passive"))
    )
    (net (code "20") (name "Net-(C31-Pad2)") (class "Default")
      (node (ref "C31") (pin "2") (pinfunction "2_2") (pintype "passive"))
      (node (ref "R10") (pin "1") (pinfunction "1_1") (pintype "passive"))
    )
    (net (code "21") (name "Net-(IC2-PA0{slash}XIN32{slash}EIC{slash}SCOM1PAD0{slash}TC2)") (class "Default")
      (node (ref "C15") (pin "2") (pinfunction "2_2") (pintype "passive"))
      (node (ref "IC2") (pin "1") (pinfunction "PA0/XIN32/EIC/SCOM1PAD0/TC2_1") (pintype "bidirectional"))
      (node (ref "U$19") (pin "P$2") (pinfunction "2_P$2") (pintype "passive"))
    )
    (net (code "22") (name "Net-(IC2-PA1{slash}XOUT32{slash}EIC{slash}SCOM1PAD1{slash}TC2)") (class "Default")
      (node (ref "C4") (pin "1") (pinfunction "1_1") (pintype "passive"))
      (node (ref "IC2") (pin "2") (pinfunction "PA1/XOUT32/EIC/SCOM1PAD1/TC2_2") (pintype "bidirectional"))
      (node (ref "U$19") (pin "P$1") (pinfunction "1_P$1") (pintype "passive"))
    )
    (net (code "23") (name "Net-(IC2-PA15{slash}XOUT{slash}EIC{slash}SCOM2PAD3+{slash}TC3)") (class "Default")
      (node (ref "IC2") (pin "24") (pinfunction "PA15/XOUT/EIC/SCOM2PAD3+/TC3_24") (pintype "bidirectional"))
      (node (ref "R11") (pin "1") (pinfunction "1_1") (pintype "passive"))
      (node (ref "TP1") (pin "TP") (pinfunction "TP_TP") (pintype "input"))
    )
    (net (code "24") (name "Net-(IC2-PA20{slash}EIC{slash}SCOM5PAD2+)") (class "Default")
      (node (ref "IC2") (pin "29") (pinfunction "PA20/EIC/SCOM5PAD2+_29") (pintype "bidirectional"))
      (node (ref "TP10") (pin "TP") (pinfunction "TP_TP") (pintype "input"))
    )
    (net (code "25") (name "Net-(IC2-VDDANA)") (class "Default")
      (node (ref "C106") (pin "1") (pinfunction "1_1") (pintype "passive"))
      (node (ref "C107") (pin "1") (pinfunction "1_1") (pintype "passive"))
      (node (ref "IC2") (pin "6") (pinfunction "VDDANA_6") (pintype "power_in"))
      (node (ref "L100") (pin "1") (pinfunction "1_1") (pintype "passive"))
    )
    (net (code "26") (name "Net-(JP3-LEFT)") (class "Default")
      (node (ref "C2") (pin "1") (pinfunction "1_1") (pintype "passive"))
      (node (ref "C38") (pin "1") (pinfunction "1_1") (pintype "passive"))
      (node (ref "JP3") (pin "TIP") (pinfunction "LEFT_TIP") (pintype "bidirectional"))
      (node (ref "R20") (pin "1") (pinfunction "1_1") (pintype "passive"))
    )
    (net (code "27") (name "Net-(JP3-PadSLEEVE)") (class "Default")
      (node (ref "JP3") (pin "SLEEVE") (pinfunction "SLEEVE_SLEEVE") (pintype "bidirectional"))
      (node (ref "R24") (pin "1") (pinfunction "1_1") (pintype "passive"))
    )
    (net (code "28") (name "Net-(JP3-RIGHT)") (class "Default")
      (node (ref "C23") (pin "1") (pinfunction "1_1") (pintype "passive"))
      (node (ref "C58") (pin "2") (pinfunction "2_2") (pintype "passive"))
      (node (ref "JP3") (pin "RING") (pinfunction "RIGHT_RING") (pintype "bidirectional"))
      (node (ref "R22") (pin "1") (pinfunction "1_1") (pintype "passive"))
    )
    (net (code "29") (name "Net-(POWER-PadC)") (class "Default")
      (node (ref "POWER") (pin "C") (pinfunction "C_C") (pintype "passive"))
      (node (ref "R30") (pin "2") (pinfunction "2_2") (pintype "passive"))
    )
    (net (code "30") (name "Net-(Q1-D)") (class "Default")
      (node (ref "L1") (pin "2") (pinfunction "2_2") (pintype "passive"))
      (node (ref "Q1") (pin "3") (pinfunction "D_3") (pintype "passive"))
      (node (ref "U$1") (pin "6") (pinfunction "E1_6") (pintype "bidirectional"))
    )
    (net (code "31") (name "Net-(Q1-G)") (class "Default")
      (node (ref "Q1") (pin "1") (pinfunction "G_1") (pintype "passive"))
      (node (ref "R48") (pin "2") (pinfunction "2_2") (pintype "passive"))
      (node (ref "U$1") (pin "4") (pinfunction "C2_4") (pintype "bidirectional"))
    )
    (net (code "32") (name "Net-(TP4-1)") (class "Default")
      (node (ref "TP4") (pin "P$1") (pinfunction "1_P$1") (pintype "bidirectional"))
      (node (ref "U$3") (pin "30") (pinfunction "CLKOUT_30") (pintype "bidirectional"))
    )
    (net (code "33") (name "Net-(U$1-B1)") (class "Default")
      (node (ref "R37") (pin "2") (pinfunction "2_2") (pintype "passive"))
      (node (ref "U$1") (pin "1") (pinfunction "C1_1") (pintype "bidirectional"))
      (node (ref "U$1") (pin "2") (pinfunction "B1_2") (pintype "bidirectional"))
      (node (ref "U$1") (pin "3") (pinfunction "B2_3") (pintype "bidirectional"))
    )
    (net (code "34") (name "Net-(U$3-BG)") (class "Default")
      (node (ref "C8") (pin "1") (pinfunction "1_1") (pintype "passive"))
      (node (ref "U$3") (pin "7") (pinfunction "BG_7") (pintype "bidirectional"))
    )
    (net (code "35") (name "Net-(U$3-XIN)") (class "Default")
      (node (ref "C6") (pin "2") (pinfunction "2_2") (pintype "passive"))
      (node (ref "U$3") (pin "38") (pinfunction "XIN_38") (pintype "bidirectional"))
      (node (ref "U$4") (pin "2") (pinfunction "2_2") (pintype "passive"))
    )
    (net (code "36") (name "Net-(U$3-XOUT)") (class "Default")
      (node (ref "C7") (pin "2") (pinfunction "2_2") (pintype "passive"))
      (node (ref "U$3") (pin "37") (pinfunction "XOUT_37") (pintype "bidirectional"))
      (node (ref "U$4") (pin "1") (pinfunction "1_1") (pintype "passive"))
    )
    (net (code "37") (name "Net-(U$8-IN1N)") (class "Default")
      (node (ref "C40") (pin "2") (pinfunction "2_2") (pintype "passive"))
      (node (ref "R12") (pin "2") (pinfunction "2_2") (pintype "passive"))
      (node (ref "R15") (pin "2") (pinfunction "2_2") (pintype "passive"))
      (node (ref "U$8") (pin "3") (pinfunction "IN1N_3") (pintype "input"))
    )
    (net (code "38") (name "Net-(U$8-IN1P)") (class "Default")
      (node (ref "C25") (pin "2") (pinfunction "2_2") (pintype "passive"))
      (node (ref "R16") (pin "2") (pinfunction "2_2") (pintype "passive"))
      (node (ref "R18") (pin "2") (pinfunction "2_2") (pintype "passive"))
      (node (ref "U$8") (pin "4") (pinfunction "IN1P_4") (pintype "input"))
    )
    (net (code "39") (name "Net-(U$8-IN2N)") (class "Default")
      (node (ref "R20") (pin "2") (pinfunction "2_2") (pintype "passive"))
      (node (ref "U$8") (pin "5") (pinfunction "IN2N_5") (pintype "input"))
    )
    (net (code "40") (name "Net-(U$8-IN2P)") (class "Default")
      (node (ref "R22") (pin "2") (pinfunction "2_2") (pintype "passive"))
      (node (ref "U$8") (pin "6") (pinfunction "IN2P_6") (pintype "input"))
    )
    (net (code "41") (name "Net-(U$8-PGA1N)") (class "Default")
      (node (ref "C57") (pin "1") (pinfunction "1_1") (pintype "passive"))
      (node (ref "U$8") (pin "1") (pinfunction "PGA1N_1") (pintype "bidirectional"))
    )
    (net (code "42") (name "Net-(U$8-PGA1P)") (class "Default")
      (node (ref "C57") (pin "2") (pinfunction "2_2") (pintype "passive"))
      (node (ref "U$8") (pin "2") (pinfunction "PGA1P_2") (pintype "bidirectional"))
    )
    (net (code "43") (name "Net-(U$8-PGA2N)") (class "Default")
      (node (ref "C56") (pin "1") (pinfunction "1_1") (pintype "passive"))
      (node (ref "U$8") (pin "7") (pinfunction "PGA2N_7") (pintype "bidirectional"))
    )
    (net (code "44") (name "Net-(U$8-PGA2P)") (class "Default")
      (node (ref "C56") (pin "2") (pinfunction "2_2") (pintype "passive"))
      (node (ref "U$8") (pin "8") (pinfunction "PGA2P_8") (pintype "bidirectional"))
    )
    (net (code "45") (name "Net-(U$8-RESP_MODN)") (class "Default")
      (node (ref "R10") (pin "2") (pinfunction "2_2") (pintype "passive"))
      (node (ref "U$8") (pin "32") (pinfunction "RESP_MODN_32") (pintype "bidirectional"))
    )
    (net (code "46") (name "Net-(U$8-RESP_MODP)") (class "Default")
      (node (ref "R4") (pin "2") (pinfunction "2_2") (pintype "passive"))
      (node (ref "U$8") (pin "31") (pinfunction "RESP_MODP_31") (pintype "bidirectional"))
    )
    (net (code "47") (name "Net-(U$8-RLDINV)") (class "Default")
      (node (ref "C62") (pin "2") (pinfunction "2_2") (pintype "passive"))
      (node (ref "R19") (pin "2") (pinfunction "2_2") (pintype "passive"))
      (node (ref "U$8") (pin "28") (pinfunction "RLDINV_28") (pintype "bidirectional"))
    )
    (net (code "48") (name "Net-(U$8-RLDIN{slash}RLDREF)") (class "Default")
      (node (ref "R21") (pin "2") (pinfunction "2_2") (pintype "passive"))
      (node (ref "U$8") (pin "29") (pinfunction "RLDIN/RLDREF_29") (pintype "bidirectional"))
    )
    (net (code "49") (name "Net-(U$8-RLDOUT)") (class "Default")
      (node (ref "C62") (pin "1") (pinfunction "1_1") (pintype "passive"))
      (node (ref "R19") (pin "1") (pinfunction "1_1") (pintype "passive"))
      (node (ref "R21") (pin "1") (pinfunction "1_1") (pintype "passive"))
      (node (ref "R24") (pin "2") (pinfunction "2_2") (pintype "passive"))
      (node (ref "U$8") (pin "30") (pinfunction "RLDOUT_30") (pintype "bidirectional"))
    )
    (net (code "50") (name "Net-(U$8-VCAP1)") (class "Default")
      (node (ref "C49") (pin "2") (pinfunction "2_2") (pintype "passive"))
      (node (ref "U$8") (pin "11") (pinfunction "VCAP1_11") (pintype "bidirectional"))
    )
    (net (code "51") (name "Net-(U$8-VCAP2)") (class "Default")
      (node (ref "C48") (pin "2") (pinfunction "2_2") (pintype "passive"))
      (node (ref "U$8") (pin "27") (pinfunction "VCAP2_27") (pintype "bidirectional"))
    )
    (net (code "52") (name "Net-(U$8-VREFP)") (class "Default")
      (node (ref "C50") (pin "2") (pinfunction "2_2") (pintype "passive"))
      (node (ref "C51") (pin "1") (pinfunction "1_1") (pintype "passive"))
      (node (ref "U$8") (pin "9") (pinfunction "VREFP_9") (pintype "bidirectional"))
    )
    (net (code "53") (name "Net-(U1-SCL)") (class "Default")
      (node (ref "K1") (pin "28") (pinfunction "28_28") (pintype "passive"))
      (node (ref "R1") (pin "1") (pinfunction "1_1") (pintype "passive"))
      (node (ref "U1") (pin "6") (pinfunction "SCL_6") (pintype "input"))
    )
    (net (code "54") (name "Net-(U1-SDA)") (class "Default")
      (node (ref "K1") (pin "27") (pinfunction "27_27") (pintype "passive"))
      (node (ref "R2") (pin "1") (pinfunction "1_1") (pintype "passive"))
      (node (ref "U1") (pin "5") (pinfunction "SDA_5") (pintype "bidirectional"))
    )
    (net (code "55") (name "Net-(U1-WP)") (class "Default")
      (node (ref "R3") (pin "1") (pinfunction "1_1") (pintype "passive"))
      (node (ref "TP3") (pin "TP") (pinfunction "TP_TP") (pintype "input"))
      (node (ref "U1") (pin "7") (pinfunction "WP_7") (pintype "input"))
    )
    (net (code "56") (name "PD_ALM") (class "Default")
      (node (ref "IC2") (pin "19") (pinfunction "PB10/EIC/SCOM4PAD2/TC5_19") (pintype "bidirectional"))
      (node (ref "U$3") (pin "23") (pinfunction "PD_ALM_23") (pintype "bidirectional"))
    )
    (net (code "57") (name "RPI_RXD") (class "Default")
      (node (ref "IC2") (pin "21") (pinfunction "PA12/I2C/EIC/SCOM2PAD0+/TC2_21") (pintype "bidirectional"))
      (node (ref "K1") (pin "10") (pinfunction "10_10") (pintype "passive"))
    )
    (net (code "58") (name "RPI_TXD") (class "Default")
      (node (ref "IC2") (pin "22") (pinfunction "PA13/I2C/EIC/SCOM2PAD1+/TC2_22") (pintype "bidirectional"))
      (node (ref "K1") (pin "8") (pinfunction "8_8") (pintype "passive"))
    )
    (net (code "59") (name "RX_ANA_SUP") (class "Default")
      (node (ref "C11") (pin "1") (pinfunction "1_1") (pintype "passive"))
      (node (ref "C18") (pin "1") (pinfunction "1_1") (pintype "passive"))
      (node (ref "D2") (pin "3") (pinfunction "A_3") (pintype "passive"))
      (node (ref "D3") (pin "3") (pinfunction "A_3") (pintype "passive"))
      (node (ref "U$3") (pin "33") (pinfunction "RX_ANA_SUP_33") (pintype "bidirectional"))
      (node (ref "U$3") (pin "39") (pinfunction "RX_ANA_SUP_39") (pintype "bidirectional"))
      (node (ref "U$7") (pin "2") (pinfunction "P$2_2") (pintype "bidirectional"))
    )
    (net (code "60") (name "RX_DIG_SUP") (class "Default")
      (node (ref "C12") (pin "1") (pinfunction "1_1") (pintype "passive"))
      (node (ref "C19") (pin "1") (pinfunction "1_1") (pintype "passive"))
      (node (ref "R47") (pin "1") (pinfunction "1_1") (pintype "passive"))
      (node (ref "U$3") (pin "31") (pinfunction "RX_DIG_SUP_31") (pintype "bidirectional"))
      (node (ref "U$9") (pin "2") (pinfunction "P$2_2") (pintype "bidirectional"))
    )
    (net (code "61") (name "SAM_RESETN") (class "Default")
      (node (ref "CON_JTAG1") (pin "10") (pinfunction "10_10") (pintype "bidirectional"))
      (node (ref "IC2") (pin "40") (pinfunction "RESETN_40") (pintype "bidirectional"))
      (node (ref "R9") (pin "2") (pinfunction "2_2") (pintype "passive"))
      (node (ref "TP2") (pin "TP") (pinfunction "TP_TP") (pintype "input"))
    )
    (net (code "62") (name "SAM_SWDCLK") (class "Default")
      (node (ref "CON_JTAG1") (pin "4") (pinfunction "4_4") (pintype "bidirectional"))
      (node (ref "IC2") (pin "45") (pinfunction "PA30/EIC/SCOM1PAD2/TC1_45") (pintype "bidirectional"))
    )
    (net (code "63") (name "SAM_SWDIO") (class "Default")
      (node (ref "CON_JTAG1") (pin "2") (pinfunction "2_2") (pintype "bidirectional"))
      (node (ref "IC2") (pin "46") (pinfunction "PA31/EIC/SCOM1PAD3/TC1_46") (pintype "bidirectional"))
    )
    (net (code "64") (name "SPO2_CS") (class "Default")
      (node (ref "IC2") (pin "7") (pinfunction "PB8/EIC/AIN2/SCOM4PAD0/TC4_7") (pintype "bidirectional"))
      (node (ref "U$3") (pin "27") (pinfunction "SPISTE_27") (pintype "bidirectional"))
    )
    (net (code "65") (name "SPO2_DRDY") (class "Default")
      (node (ref "IC2") (pin "3") (pinfunction "PA2/EIC/AIN0_3") (pintype "bidirectional"))
      (node (ref "U$3") (pin "28") (pinfunction "ADC_RDY_28") (pintype "bidirectional"))
    )
    (net (code "66") (name "SPO2_MISO") (class "Default")
      (node (ref "IC2") (pin "9") (pinfunction "PA4/EIC/REF/AIN4/SCOM0PAD0/TC0_9") (pintype "bidirectional"))
      (node (ref "U$3") (pin "25") (pinfunction "SPISOMI_25") (pintype "bidirectional"))
    )
    (net (code "67") (name "SPO2_MOSI") (class "Default")
      (node (ref "IC2") (pin "11") (pinfunction "PA6/EIC/AIN6/SCOM0PAD2/TC1_11") (pintype "bidirectional"))
      (node (ref "U$3") (pin "26") (pinfunction "SPISIMO_26") (pintype "bidirectional"))
    )
    (net (code "68") (name "SPO2_SCK") (class "Default")
      (node (ref "IC2") (pin "12") (pinfunction "PA7/EIC/AIN7/SCOM0PAD3/TC1_12") (pintype "bidirectional"))
      (node (ref "U$3") (pin "24") (pinfunction "SCLK_24") (pintype "bidirectional"))
    )
    (net (code "69") (name "SPO2_START") (class "Default")
      (node (ref "IC2") (pin "8") (pinfunction "PB9/EIC/AIN3/SCOM4PAD1//TC4_8") (pintype "bidirectional"))
      (node (ref "U$3") (pin "20") (pinfunction "AFE_~{PDN}_20") (pintype "bidirectional"))
    )
    (net (code "70") (name "TARGET_USB_N") (class "Default")
      (node (ref "IC2") (pin "33") (pinfunction "PA24/EIC/SCOM3PAD2+/TC5_33") (pintype "bidirectional"))
      (node (ref "R14") (pin "1") (pinfunction "1_1") (pintype "passive"))
    )
    (net (code "71") (name "TARGET_USB_P") (class "Default")
      (node (ref "IC2") (pin "34") (pinfunction "PA25/EIC/SCOM3PAD3+/TC5_34") (pintype "bidirectional"))
      (node (ref "R13") (pin "1") (pinfunction "1_1") (pintype "passive"))
    )
    (net (code "72") (name "TMP_SCL") (class "Default")
      (node (ref "IC2") (pin "26") (pinfunction "PA17/I2C/EIC/SCOM1PAD1+/TC2_26") (pintype "bidirectional"))
      (node (ref "R5") (pin "2") (pinfunction "2_2") (pintype "passive"))
      (node (ref "SV2") (pin "2") (pinfunction "2_2") (pintype "passive"))
    )
    (net (code "73") (name "TMP_SDA") (class "Default")
      (node (ref "IC2") (pin "25") (pinfunction "PA16/I2C/EIC/SCOM1PAD0+/TC2_25") (pintype "bidirectional"))
      (node (ref "R6") (pin "2") (pinfunction "2_2") (pintype "passive"))
      (node (ref "SV2") (pin "3") (pinfunction "3_3") (pintype "passive"))
    )
    (net (code "74") (name "TXN") (class "Default")
      (node (ref "D1") (pin "1") (pinfunction "CA_1") (pintype "passive"))
      (node (ref "U$3") (pin "14") (pinfunction "TXN_14") (pintype "bidirectional"))
      (node (ref "X1") (pin "3") (pinfunction "3_3") (pintype "passive"))
    )
    (net (code "75") (name "TXP") (class "Default")
      (node (ref "D5") (pin "1") (pinfunction "CA_1") (pintype "passive"))
      (node (ref "U$3") (pin "15") (pinfunction "TXP_15") (pintype "bidirectional"))
      (node (ref "X1") (pin "2") (pinfunction "2_2") (pintype "passive"))
    )
    (net (code "76") (name "TX_CTRL_SUP") (class "Default")
      (node (ref "C27") (pin "1") (pinfunction "1_1") (pintype "passive"))
      (node (ref "C9") (pin "1") (pinfunction "1_1") (pintype "passive"))
      (node (ref "U$10") (pin "2") (pinfunction "P$2_2") (pintype "bidirectional"))
      (node (ref "U$3") (pin "11") (pinfunction "TX_CTRL_SUP_11") (pintype "bidirectional"))
    )
    (net (code "77") (name "USB_N") (class "Default")
      (node (ref "JP5") (pin "2") (pinfunction "D-_2") (pintype "bidirectional"))
      (node (ref "R14") (pin "2") (pinfunction "2_2") (pintype "passive"))
    )
    (net (code "78") (name "USB_P") (class "Default")
      (node (ref "JP5") (pin "3") (pinfunction "D+_3") (pintype "bidirectional"))
      (node (ref "R13") (pin "2") (pinfunction "2_2") (pintype "passive"))
    )
    (net (code "79") (name "VCCIO") (class "Default")
      (node (ref "C3") (pin "1") (pinfunction "1_1") (pintype "passive"))
      (node (ref "JP5") (pin "1") (pinfunction "VCC_1") (pintype "bidirectional"))
      (node (ref "L1") (pin "1") (pinfunction "1_1") (pintype "passive"))
    )
    (net (code "80") (name "VCM") (class "Default")
      (node (ref "C13") (pin "1") (pinfunction "1_1") (pintype "passive"))
      (node (ref "U$3") (pin "4") (pinfunction "VCM_4") (pintype "bidirectional"))
    )
    (net (code "81") (name "VDDCORE") (class "Default")
      (node (ref "C102") (pin "1") (pinfunction "1_1") (pintype "passive"))
      (node (ref "IC2") (pin "43") (pinfunction "VDDCORE1_43") (pintype "input"))
    )
    (net (code "82") (name "unconnected-(CON_JTAG1-Pad6)") (class "Default")
      (node (ref "CON_JTAG1") (pin "6") (pinfunction "6_6") (pintype "bidirectional"))
    )
    (net (code "83") (name "unconnected-(CON_JTAG1-Pad7)") (class "Default")
      (node (ref "CON_JTAG1") (pin "7") (pinfunction "7_7") (pintype "bidirectional"))
    )
    (net (code "84") (name "unconnected-(CON_JTAG1-Pad8)") (class "Default")
      (node (ref "CON_JTAG1") (pin "8") (pinfunction "8_8") (pintype "bidirectional"))
    )
    (net (code "85") (name "unconnected-(IC2-PA3{slash}EIC{slash}REF{slash}AIN1-Pad4)") (class "Default")
      (node (ref "IC2") (pin "4") (pinfunction "PA3/EIC/REF/AIN1_4") (pintype "bidirectional"))
    )
    (net (code "86") (name "unconnected-(IC2-PA14{slash}XIN{slash}EIC{slash}SCOM2PAD2+{slash}TC3-Pad23)") (class "Default")
      (node (ref "IC2") (pin "23") (pinfunction "PA14/XIN/EIC/SCOM2PAD2+/TC3_23") (pintype "bidirectional"))
    )
    (net (code "87") (name "unconnected-(IC2-PA21{slash}EIC{slash}SCOM5PAD3+-Pad30)") (class "Default")
      (node (ref "IC2") (pin "30") (pinfunction "PA21/EIC/SCOM5PAD3+_30") (pintype "bidirectional"))
    )
    (net (code "88") (name "unconnected-(IC2-PA22{slash}I2C{slash}EIC{slash}SCOM5PAD0+{slash}TC4-Pad31)") (class "Default")
      (node (ref "IC2") (pin "31") (pinfunction "PA22/I2C/EIC/SCOM5PAD0+/TC4_31") (pintype "bidirectional"))
    )
    (net (code "89") (name "unconnected-(IC2-PA23{slash}I2C{slash}EIC{slash}SCOM5PAD1+{slash}TC4-Pad32)") (class "Default")
      (node (ref "IC2") (pin "32") (pinfunction "PA23/I2C/EIC/SCOM5PAD1+/TC4_32") (pintype "bidirectional"))
    )
    (net (code "90") (name "unconnected-(IC2-PA27{slash}EIC-Pad39)") (class "Default")
      (node (ref "IC2") (pin "39") (pinfunction "PA27/EIC_39") (pintype "bidirectional"))
    )
    (net (code "91") (name "unconnected-(IC2-PA28{slash}EIC-Pad41)") (class "Default")
      (node (ref "IC2") (pin "41") (pinfunction "PA28/EIC_41") (pintype "bidirectional"))
    )
    (net (code "92") (name "unconnected-(IC2-PB2{slash}EIC{slash}AIN10{slash}SCOM5PAD0-Pad47)") (class "Default")
      (node (ref "IC2") (pin "47") (pinfunction "PB2/EIC/AIN10/SCOM5PAD0_47") (pintype "bidirectional"))
    )
    (net (code "93") (name "unconnected-(IC2-PB3{slash}EIC{slash}AIN11{slash}SCOM5PAD1-Pad48)") (class "Default")
      (node (ref "IC2") (pin "48") (pinfunction "PB3/EIC/AIN11/SCOM5PAD1_48") (pintype "bidirectional"))
    )
    (net (code "94") (name "unconnected-(K1-Pad1)") (class "Default")
      (node (ref "K1") (pin "1") (pinfunction "1_1") (pintype "passive"))
    )
    (net (code "95") (name "unconnected-(K1-Pad3)") (class "Default")
      (node (ref "K1") (pin "3") (pinfunction "3_3") (pintype "passive"))
    )
    (net (code "96") (name "unconnected-(K1-Pad5)") (class "Default")
      (node (ref "K1") (pin "5") (pinfunction "5_5") (pintype "passive"))
    )
    (net (code "97") (name "unconnected-(K1-Pad7)") (class "Default")
      (node (ref "K1") (pin "7") (pinfunction "7_7") (pintype "passive"))
    )
    (net (code "98") (name "unconnected-(K1-Pad11)") (class "Default")
      (node (ref "K1") (pin "11") (pinfunction "11_11") (pintype "passive"))
    )
    (net (code "99") (name "unconnected-(K1-Pad12)") (class "Default")
      (node (ref "K1") (pin "12") (pinfunction "12_12") (pintype "passive"))
    )
    (net (code "100") (name "unconnected-(K1-Pad13)") (class "Default")
      (node (ref "K1") (pin "13") (pinfunction "13_13") (pintype "passive"))
    )
    (net (code "101") (name "unconnected-(K1-Pad15)") (class "Default")
      (node (ref "K1") (pin "15") (pinfunction "15_15") (pintype "passive"))
    )
    (net (code "102") (name "unconnected-(K1-Pad16)") (class "Default")
      (node (ref "K1") (pin "16") (pinfunction "16_16") (pintype "passive"))
    )
    (net (code "103") (name "unconnected-(K1-Pad17)") (class "Default")
      (node (ref "K1") (pin "17") (pinfunction "17_17") (pintype "passive"))
    )
    (net (code "104") (name "unconnected-(K1-Pad18)") (class "Default")
      (node (ref "K1") (pin "18") (pinfunction "18_18") (pintype "passive"))
    )
    (net (code "105") (name "unconnected-(K1-Pad19)") (class "Default")
      (node (ref "K1") (pin "19") (pinfunction "19_19") (pintype "passive"))
    )
    (net (code "106") (name "unconnected-(K1-Pad21)") (class "Default")
      (node (ref "K1") (pin "21") (pinfunction "21_21") (pintype "passive"))
    )
    (net (code "107") (name "unconnected-(K1-Pad22)") (class "Default")
      (node (ref "K1") (pin "22") (pinfunction "22_22") (pintype "passive"))
    )
    (net (code "108") (name "unconnected-(K1-Pad23)") (class "Default")
      (node (ref "K1") (pin "23") (pinfunction "23_23") (pintype "passive"))
    )
    (net (code "109") (name "unconnected-(K1-Pad24)") (class "Default")
      (node (ref "K1") (pin "24") (pinfunction "24_24") (pintype "passive"))
    )
    (net (code "110") (name "unconnected-(K1-Pad26)") (class "Default")
      (node (ref "K1") (pin "26") (pinfunction "26_26") (pintype "passive"))
    )
    (net (code "111") (name "unconnected-(K1-Pad29)") (class "Default")
      (node (ref "K1") (pin "29") (pinfunction "29_29") (pintype "passive"))
    )
    (net (code "112") (name "unconnected-(K1-Pad31)") (class "Default")
      (node (ref "K1") (pin "31") (pinfunction "31_31") (pintype "passive"))
    )
    (net (code "113") (name "unconnected-(K1-Pad32)") (class "Default")
      (node (ref "K1") (pin "32") (pinfunction "32_32") (pintype "passive"))
    )
    (net (code "114") (name "unconnected-(K1-Pad33)") (class "Default")
      (node (ref "K1") (pin "33") (pinfunction "33_33") (pintype "passive"))
    )
    (net (code "115") (name "unconnected-(K1-Pad35)") (class "Default")
      (node (ref "K1") (pin "35") (pinfunction "35_35") (pintype "passive"))
    )
    (net (code "116") (name "unconnected-(K1-Pad36)") (class "Default")
      (node (ref "K1") (pin "36") (pinfunction "36_36") (pintype "passive"))
    )
    (net (code "117") (name "unconnected-(K1-Pad37)") (class "Default")
      (node (ref "K1") (pin "37") (pinfunction "37_37") (pintype "passive"))
    )
    (net (code "118") (name "unconnected-(K1-Pad38)") (class "Default")
      (node (ref "K1") (pin "38") (pinfunction "38_38") (pintype "passive"))
    )
    (net (code "119") (name "unconnected-(K1-Pad40)") (class "Default")
      (node (ref "K1") (pin "40") (pinfunction "40_40") (pintype "passive"))
    )
    (net (code "120") (name "unconnected-(U$3-DIAG_END-Pad21)") (class "Default")
      (node (ref "U$3") (pin "21") (pinfunction "DIAG_END_21") (pintype "bidirectional"))
    )
    (net (code "121") (name "unconnected-(U$3-DNC-Pad5)") (class "Default")
      (node (ref "U$3") (pin "5") (pinfunction "DNC_5") (pintype "bidirectional"))
    )
    (net (code "122") (name "unconnected-(U$3-DNC-Pad6)") (class "Default")
      (node (ref "U$3") (pin "6") (pinfunction "DNC_6") (pintype "bidirectional"))
    )
    (net (code "123") (name "unconnected-(U$3-DNC-Pad10)") (class "Default")
      (node (ref "U$3") (pin "10") (pinfunction "DNC_10") (pintype "bidirectional"))
    )
    (net (code "124") (name "unconnected-(U$3-DNC-Pad34)") (class "Default")
      (node (ref "U$3") (pin "34") (pinfunction "DNC_34") (pintype "bidirectional"))
    )
    (net (code "125") (name "unconnected-(U$3-DNC-Pad35)") (class "Default")
      (node (ref "U$3") (pin "35") (pinfunction "DNC_35") (pintype "bidirectional"))
    )
    (net (code "126") (name "unconnected-(U$3-RSVD-Pad9)") (class "Default")
      (node (ref "U$3") (pin "9") (pinfunction "RSVD_9") (pintype "bidirectional"))
    )
    (net (code "127") (name "unconnected-(U$8-CLK-Pad17)") (class "Default")
      (node (ref "U$8") (pin "17") (pinfunction "CLK_17") (pintype "bidirectional"))
    )
    (net (code "128") (name "unconnected-(U$8-GPIO1-Pad26)") (class "Default")
      (node (ref "U$8") (pin "26") (pinfunction "GPIO1_26") (pintype "bidirectional"))
    )
    (net (code "129") (name "unconnected-(U$8-GPIO2-Pad25)") (class "Default")
      (node (ref "U$8") (pin "25") (pinfunction "GPIO2_25") (pintype "bidirectional"))
    )
    (net (code "130") (name "unconnected-(U3-BP-Pad4)") (class "Default")
      (node (ref "U3") (pin "4") (pinfunction "BP_4") (pintype "input"))
    )
    (net (code "131") (name "unconnected-(X1-Pad1)") (class "Default")
      (node (ref "X1") (pin "1") (pinfunction "1_1") (pintype "passive"))
    )
    (net (code "132") (name "unconnected-(X1-Pad4)") (class "Default")
      (node (ref "X1") (pin "4") (pinfunction "4_4") (pintype "passive"))
    )
    (net (code "133") (name "unconnected-(X1-Pad6)") (class "Default")
      (node (ref "X1") (pin "6") (pinfunction "6_6") (pintype "passive"))
    )
    (net (code "134") (name "unconnected-(X1-Pad8)") (class "Default")
      (node (ref "X1") (pin "8") (pinfunction "8_8") (pintype "passive"))
    )
    (net (code "135") (name "~{ADC_RESET}") (class "Default")
      (node (ref "R47") (pin "2") (pinfunction "2_2") (pintype "passive"))
      (node (ref "U$3") (pin "29") (pinfunction "~{RESET}_29") (pintype "bidirectional"))
    )
  )
)
